# Memory.net
KiCad netlist of a schematic drawn in Altium Designer
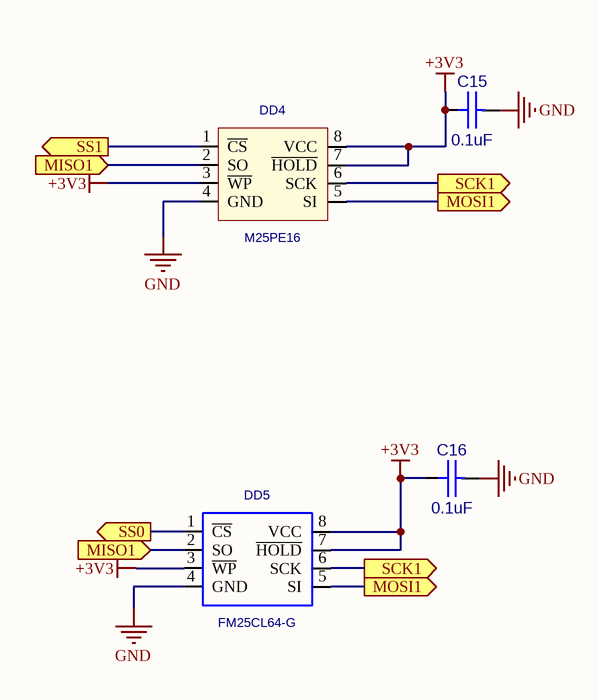
[diagram p0: Memory.SchDoc]

(export (version "E")
  (design (tool "Eeschema 10.0.6"))
  (components
    (comp (ref "C15")
      (value "0.1uF")
      (footprint "CC0603")
      (description "CC0603")
      (libsource (lib "gprs_modem_2") (part "CC0603"))
    )
    (comp (ref "C16")
      (value "0.1uF")
      (footprint "CC0603")
      (description "CC0603")
      (libsource (lib "gprs_modem_2") (part "CC0603"))
    )
    (comp (ref "DD4")
      (value "M25PE16")
      (footprint "EIAJ_SO8")
      (description "S25FL016A0LMFI01")
      (libsource (lib "gprs_modem_2") (part "S25FL016A0LMFI01"))
    )
    (comp (ref "DD5")
      (value "FM25CL64-G")
      (footprint "SO-8")
      (libsource (lib "gprs_modem_2") (part "FM25CL64-G"))
    )
  )
  (nets
    (net (code "1") (name "+3V3") (class "Default")
      (node (ref "C15") (pin "1") (pinfunction "A_1") (pintype "passive"))
      (node (ref "C16") (pin "1") (pinfunction "A_1") (pintype "passive"))
      (node (ref "DD4") (pin "3") (pinfunction "~{WP}_3") (pintype "passive"))
      (node (ref "DD4") (pin "7") (pinfunction "~{HOLD}_7") (pintype "passive"))
      (node (ref "DD4") (pin "8") (pinfunction "VCC_8") (pintype "passive"))
      (node (ref "DD5") (pin "3") (pinfunction "~{WP}_3") (pintype "passive"))
      (node (ref "DD5") (pin "7") (pinfunction "~{HOLD}_7") (pintype "passive"))
      (node (ref "DD5") (pin "8") (pinfunction "VCC_8") (pintype "passive"))
    )
    (net (code "2") (name "/MISO1") (class "Default")
      (node (ref "DD4") (pin "2") (pinfunction "SO_2") (pintype "passive"))
      (node (ref "DD5") (pin "2") (pinfunction "SO_2") (pintype "passive"))
    )
    (net (code "3") (name "/MOSI1") (class "Default")
      (node (ref "DD4") (pin "5") (pinfunction "SI_5") (pintype "passive"))
      (node (ref "DD5") (pin "5") (pinfunction "SI_5") (pintype "passive"))
    )
    (net (code "4") (name "/SCK1") (class "Default")
      (node (ref "DD4") (pin "6") (pinfunction "SCK_6") (pintype "passive"))
      (node (ref "DD5") (pin "6") (pinfunction "SCK_6") (pintype "passive"))
    )
    (net (code "5") (name "/SS0") (class "Default")
      (node (ref "DD5") (pin "1") (pinfunction "~{CS}_1") (pintype "passive"))
    )
    (net (code "6") (name "/SS1") (class "Default")
      (node (ref "DD4") (pin "1") (pinfunction "~{CS}_1") (pintype "passive"))
    )
    (net (code "7") (name "GND") (class "Default")
      (node (ref "C15") (pin "2") (pinfunction "B_2") (pintype "passive"))
      (node (ref "C16") (pin "2") (pinfunction "B_2") (pintype "passive"))
      (node (ref "DD4") (pin "4") (pinfunction "GND_4") (pintype "passive"))
      (node (ref "DD5") (pin "4") (pinfunction "GND_4") (pintype "passive"))
    )
  )
)
